# stickie.net
KiCad netlist of a schematic drawn in EAGLE
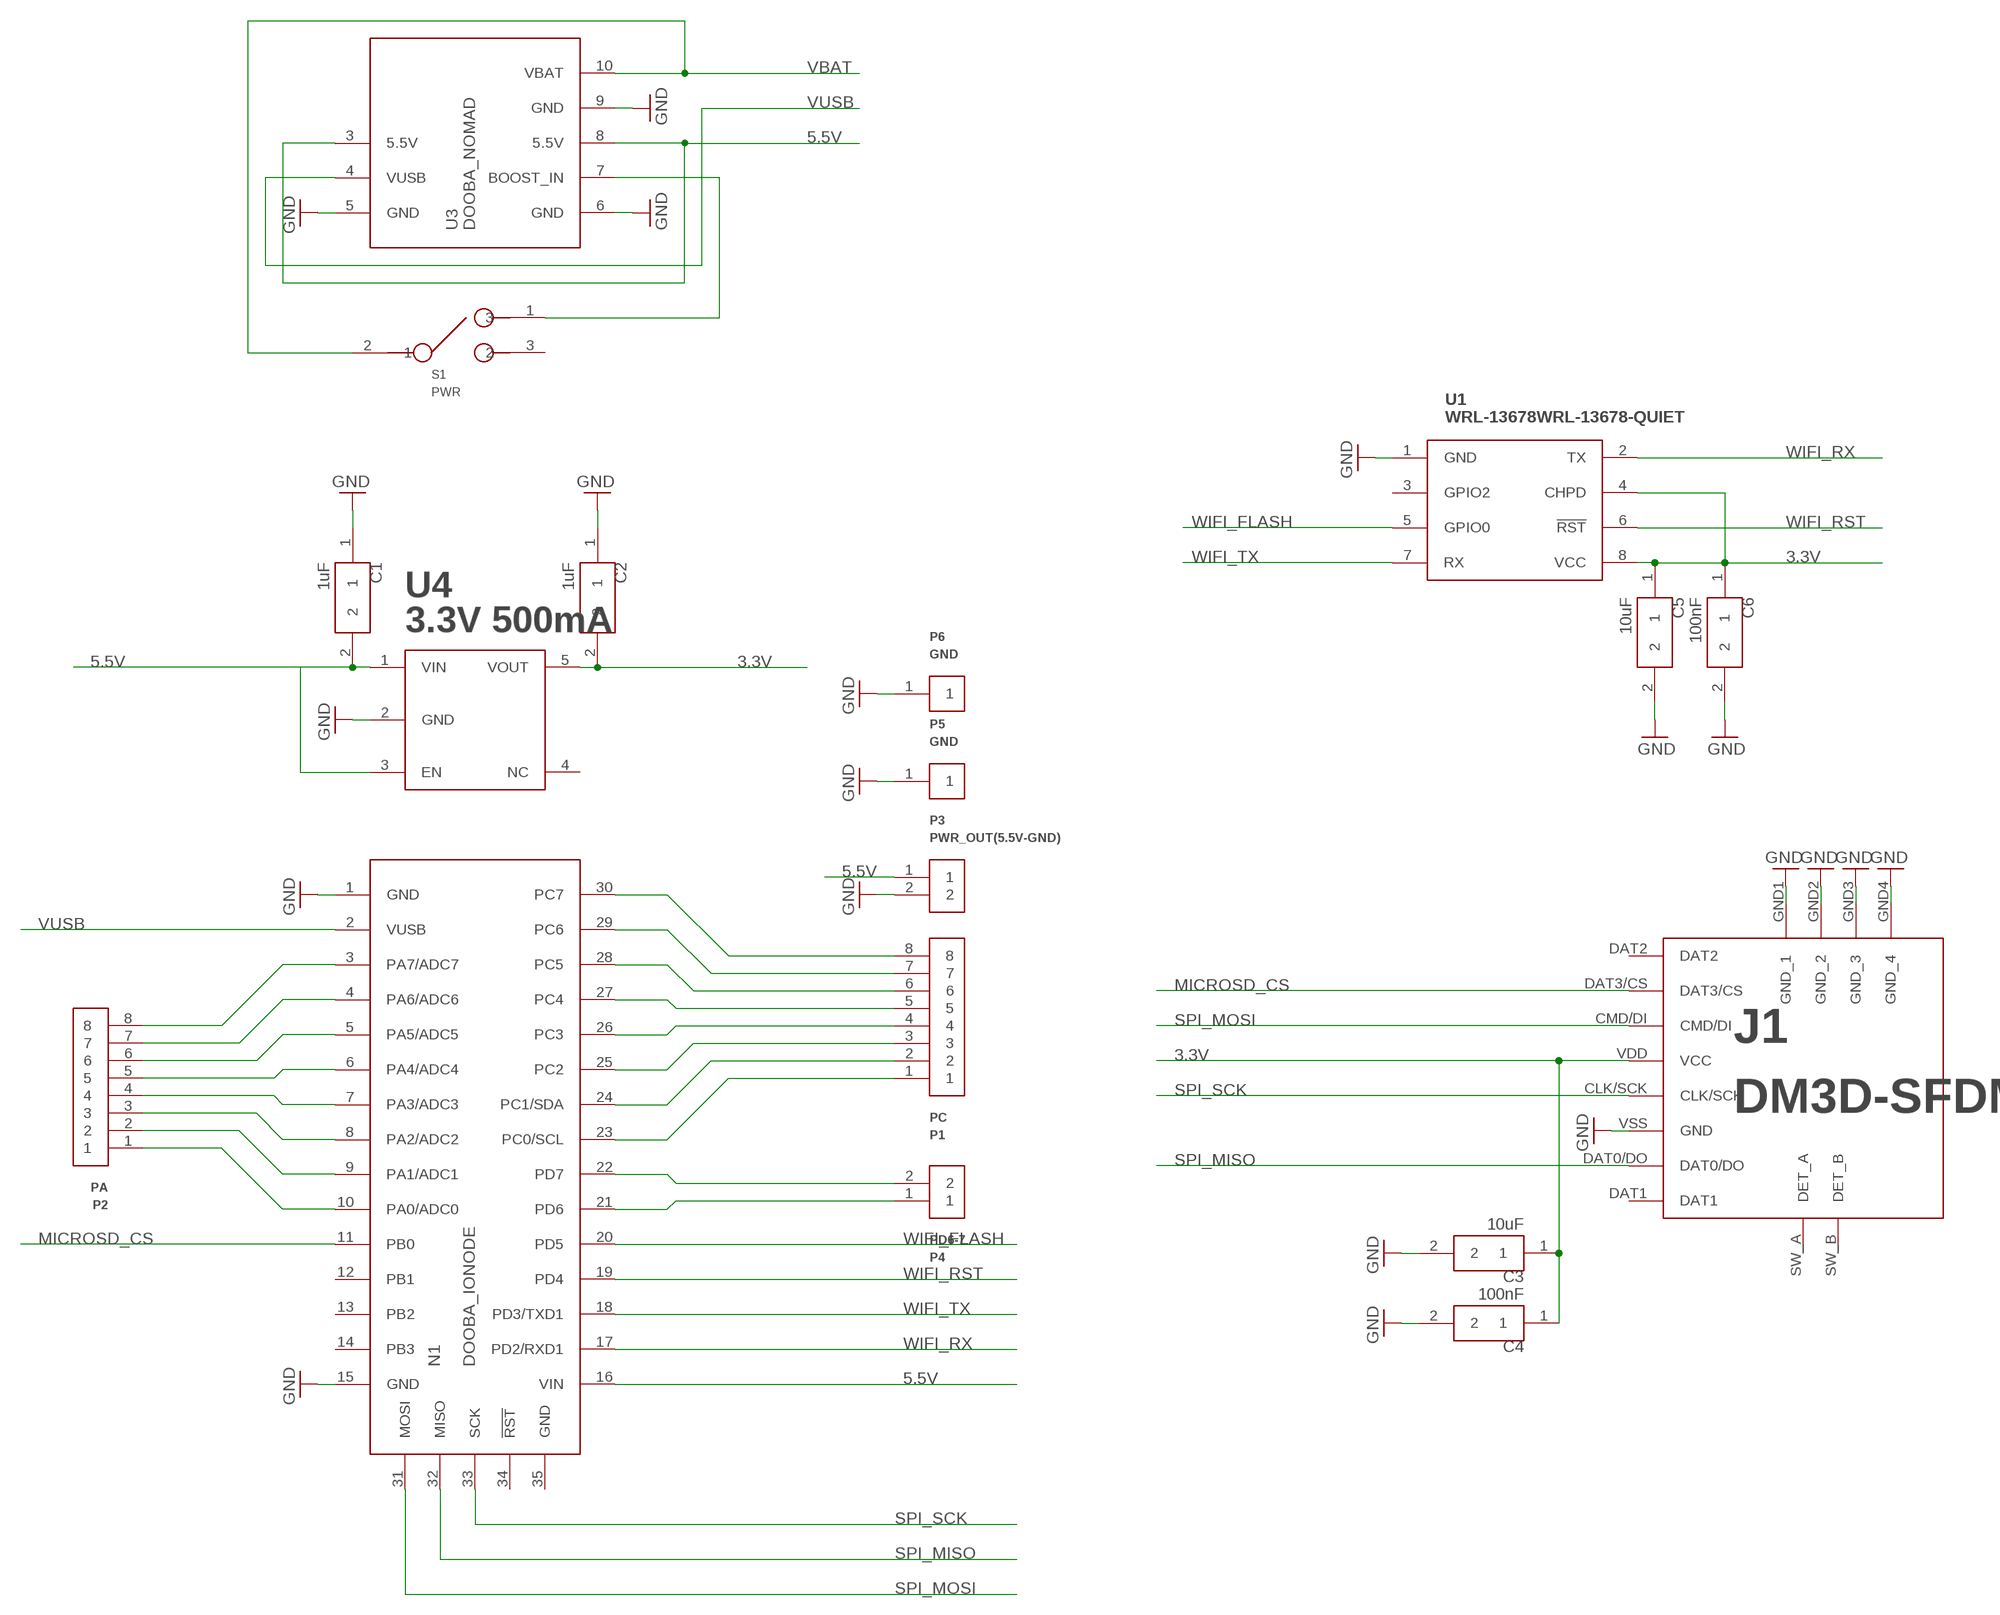
[diagram p0: schematic, sheet 1]

(export (version "E")
  (design (tool "Eeschema 10.0.6"))
  (components
    (comp (ref "C1")
      (value "1uF")
      (footprint "eagle-import:0805")
      (libsource (lib "eagle-import") (part "CAP0805"))
    )
    (comp (ref "C2")
      (value "1uF")
      (footprint "eagle-import:0805")
      (libsource (lib "eagle-import") (part "CAP0805"))
    )
    (comp (ref "C3")
      (value "10uF")
      (footprint "eagle-import:0805")
      (libsource (lib "eagle-import") (part "CAP0805"))
    )
    (comp (ref "C4")
      (value "100nF")
      (footprint "eagle-import:0805")
      (libsource (lib "eagle-import") (part "CAP0805"))
    )
    (comp (ref "C5")
      (value "10uF")
      (footprint "eagle-import:0805")
      (libsource (lib "eagle-import") (part "CAP0805"))
    )
    (comp (ref "C6")
      (value "100nF")
      (footprint "eagle-import:0805")
      (libsource (lib "eagle-import") (part "CAP0805"))
    )
    (comp (ref "J1")
      (value "DM3D-SFDM")
      (footprint "eagle-import:DM3D-SF")
      (libsource (lib "eagle-import") (part "DM3D-SFDM"))
    )
    (comp (ref "N1")
      (value "DOOBA_IONODE")
      (footprint "eagle-import:DOOBA_IONODE")
      (libsource (lib "eagle-import") (part "DOOBA_IONODE"))
    )
    (comp (ref "P1")
      (value "PC")
      (footprint "eagle-import:PIN_8")
      (libsource (lib "eagle-import") (part "PIN_8"))
    )
    (comp (ref "P2")
      (value "PA")
      (footprint "eagle-import:PIN_8")
      (libsource (lib "eagle-import") (part "PIN_8"))
    )
    (comp (ref "P3")
      (value "PWR_OUT(5.5V-GND)")
      (footprint "eagle-import:PIN_2")
      (libsource (lib "eagle-import") (part "PIN_2"))
    )
    (comp (ref "P4")
      (value "PD6-7")
      (footprint "eagle-import:PIN_2")
      (libsource (lib "eagle-import") (part "PIN_2"))
    )
    (comp (ref "P5")
      (value "GND")
      (footprint "eagle-import:PIN_1")
      (libsource (lib "eagle-import") (part "PIN_1"))
    )
    (comp (ref "P6")
      (value "GND")
      (footprint "eagle-import:PIN_1")
      (libsource (lib "eagle-import") (part "PIN_1"))
    )
    (comp (ref "S1")
      (value "PWR")
      (footprint "eagle-import:JS102011")
      (libsource (lib "eagle-import") (part "SWITCH_SPDT"))
    )
    (comp (ref "U1")
      (value "WRL-13678WRL-13678-QUIET")
      (footprint "eagle-import:WRL-13678-QUIET")
      (libsource (lib "eagle-import") (part "WRL-13678WRL-13678-QUIET"))
    )
    (comp (ref "U3")
      (value "DOOBA_NOMAD")
      (footprint "eagle-import:DOOBA_NOMAD")
      (libsource (lib "eagle-import") (part "DOOBA_NOMAD"))
    )
    (comp (ref "U4")
      (value "3.3V 500mA")
      (footprint "eagle-import:SOT23-5")
      (libsource (lib "eagle-import") (part "LP3985SOT23-5"))
    )
  )
  (nets
    (net (code "1") (name "/3.3V") (class "Default")
      (node (ref "C2") (pin "2") (pinfunction "2_2") (pintype "bidirectional"))
      (node (ref "C3") (pin "1") (pinfunction "1_1") (pintype "bidirectional"))
      (node (ref "C4") (pin "1") (pinfunction "1_1") (pintype "bidirectional"))
      (node (ref "C5") (pin "1") (pinfunction "1_1") (pintype "bidirectional"))
      (node (ref "C6") (pin "1") (pinfunction "1_1") (pintype "bidirectional"))
      (node (ref "J1") (pin "VDD") (pinfunction "VCC_VDD") (pintype "bidirectional"))
      (node (ref "U1") (pin "4") (pinfunction "CHPD_4") (pintype "bidirectional"))
      (node (ref "U1") (pin "8") (pinfunction "VCC_8") (pintype "bidirectional"))
      (node (ref "U4") (pin "5") (pinfunction "VOUT_5") (pintype "bidirectional"))
    )
    (net (code "2") (name "/5.5V") (class "Default")
      (node (ref "C1") (pin "2") (pinfunction "2_2") (pintype "bidirectional"))
      (node (ref "N1") (pin "16") (pinfunction "VIN_16") (pintype "bidirectional"))
      (node (ref "P3") (pin "1") (pinfunction "1_1") (pintype "bidirectional"))
      (node (ref "U3") (pin "3") (pinfunction "5.5V_3") (pintype "bidirectional"))
      (node (ref "U3") (pin "8") (pinfunction "5.5V_8") (pintype "bidirectional"))
      (node (ref "U4") (pin "1") (pinfunction "VIN_1") (pintype "bidirectional"))
      (node (ref "U4") (pin "3") (pinfunction "EN_3") (pintype "bidirectional"))
    )
    (net (code "3") (name "/MICROSD_CS") (class "Default")
      (node (ref "J1") (pin "DAT3/CS") (pinfunction "DAT3/CS_DAT3/CS") (pintype "bidirectional"))
      (node (ref "N1") (pin "11") (pinfunction "PB0_11") (pintype "bidirectional"))
    )
    (net (code "4") (name "/SPI_MISO") (class "Default")
      (node (ref "J1") (pin "DAT0/DO") (pinfunction "DAT0/DO_DAT0/DO") (pintype "bidirectional"))
      (node (ref "N1") (pin "32") (pinfunction "MISO_32") (pintype "bidirectional"))
    )
    (net (code "5") (name "/SPI_MOSI") (class "Default")
      (node (ref "J1") (pin "CMD/DI") (pinfunction "CMD/DI_CMD/DI") (pintype "bidirectional"))
      (node (ref "N1") (pin "31") (pinfunction "MOSI_31") (pintype "bidirectional"))
    )
    (net (code "6") (name "/SPI_SCK") (class "Default")
      (node (ref "J1") (pin "CLK/SCK") (pinfunction "CLK/SCK_CLK/SCK") (pintype "bidirectional"))
      (node (ref "N1") (pin "33") (pinfunction "SCK_33") (pintype "bidirectional"))
    )
    (net (code "7") (name "/VBAT") (class "Default")
      (node (ref "S1") (pin "2") (pinfunction "1_2") (pintype "bidirectional"))
      (node (ref "U3") (pin "10") (pinfunction "VBAT_10") (pintype "bidirectional"))
    )
    (net (code "8") (name "/VUSB") (class "Default")
      (node (ref "N1") (pin "2") (pinfunction "VUSB_2") (pintype "bidirectional"))
      (node (ref "U3") (pin "4") (pinfunction "VUSB_4") (pintype "bidirectional"))
    )
    (net (code "9") (name "/WIFI_FLASH") (class "Default")
      (node (ref "N1") (pin "20") (pinfunction "PD5_20") (pintype "bidirectional"))
      (node (ref "U1") (pin "5") (pinfunction "GPIO0_5") (pintype "bidirectional"))
    )
    (net (code "10") (name "/WIFI_RST") (class "Default")
      (node (ref "N1") (pin "19") (pinfunction "PD4_19") (pintype "bidirectional"))
      (node (ref "U1") (pin "6") (pinfunction "~{RST}_6") (pintype "bidirectional"))
    )
    (net (code "11") (name "/WIFI_RX") (class "Default")
      (node (ref "N1") (pin "17") (pinfunction "PD2/RXD1_17") (pintype "bidirectional"))
      (node (ref "U1") (pin "2") (pinfunction "TX_2") (pintype "bidirectional"))
    )
    (net (code "12") (name "/WIFI_TX") (class "Default")
      (node (ref "N1") (pin "18") (pinfunction "PD3/TXD1_18") (pintype "bidirectional"))
      (node (ref "U1") (pin "7") (pinfunction "RX_7") (pintype "bidirectional"))
    )
    (net (code "13") (name "GND") (class "Default")
      (node (ref "C1") (pin "1") (pinfunction "1_1") (pintype "bidirectional"))
      (node (ref "C2") (pin "1") (pinfunction "1_1") (pintype "bidirectional"))
      (node (ref "C3") (pin "2") (pinfunction "2_2") (pintype "bidirectional"))
      (node (ref "C4") (pin "2") (pinfunction "2_2") (pintype "bidirectional"))
      (node (ref "C5") (pin "2") (pinfunction "2_2") (pintype "bidirectional"))
      (node (ref "C6") (pin "2") (pinfunction "2_2") (pintype "bidirectional"))
      (node (ref "J1") (pin "GND1") (pinfunction "GND_1_GND1") (pintype "bidirectional"))
      (node (ref "J1") (pin "GND2") (pinfunction "GND_2_GND2") (pintype "bidirectional"))
      (node (ref "J1") (pin "GND3") (pinfunction "GND_3_GND3") (pintype "bidirectional"))
      (node (ref "J1") (pin "GND4") (pinfunction "GND_4_GND4") (pintype "bidirectional"))
      (node (ref "J1") (pin "VSS") (pinfunction "GND_VSS") (pintype "bidirectional"))
      (node (ref "N1") (pin "1") (pinfunction "GND_1") (pintype "bidirectional"))
      (node (ref "N1") (pin "15") (pinfunction "GND_15") (pintype "bidirectional"))
      (node (ref "P3") (pin "2") (pinfunction "2_2") (pintype "bidirectional"))
      (node (ref "P5") (pin "1") (pinfunction "1_1") (pintype "bidirectional"))
      (node (ref "P6") (pin "1") (pinfunction "1_1") (pintype "bidirectional"))
      (node (ref "U1") (pin "1") (pinfunction "GND_1") (pintype "bidirectional"))
      (node (ref "U3") (pin "5") (pinfunction "GND_5") (pintype "bidirectional"))
      (node (ref "U3") (pin "6") (pinfunction "GND_6") (pintype "bidirectional"))
      (node (ref "U3") (pin "9") (pinfunction "GND_9") (pintype "bidirectional"))
      (node (ref "U4") (pin "2") (pinfunction "GND_2") (pintype "bidirectional"))
    )
    (net (code "14") (name "Net-(N1-PA0{slash}ADC0)") (class "Default")
      (node (ref "N1") (pin "10") (pinfunction "PA0/ADC0_10") (pintype "bidirectional"))
      (node (ref "P2") (pin "1") (pinfunction "1_1") (pintype "bidirectional"))
    )
    (net (code "15") (name "Net-(N1-PA1{slash}ADC1)") (class "Default")
      (node (ref "N1") (pin "9") (pinfunction "PA1/ADC1_9") (pintype "bidirectional"))
      (node (ref "P2") (pin "2") (pinfunction "2_2") (pintype "bidirectional"))
    )
    (net (code "16") (name "Net-(N1-PA2{slash}ADC2)") (class "Default")
      (node (ref "N1") (pin "8") (pinfunction "PA2/ADC2_8") (pintype "bidirectional"))
      (node (ref "P2") (pin "3") (pinfunction "3_3") (pintype "bidirectional"))
    )
    (net (code "17") (name "Net-(N1-PA3{slash}ADC3)") (class "Default")
      (node (ref "N1") (pin "7") (pinfunction "PA3/ADC3_7") (pintype "bidirectional"))
      (node (ref "P2") (pin "4") (pinfunction "4_4") (pintype "bidirectional"))
    )
    (net (code "18") (name "Net-(N1-PA4{slash}ADC4)") (class "Default")
      (node (ref "N1") (pin "6") (pinfunction "PA4/ADC4_6") (pintype "bidirectional"))
      (node (ref "P2") (pin "5") (pinfunction "5_5") (pintype "bidirectional"))
    )
    (net (code "19") (name "Net-(N1-PA5{slash}ADC5)") (class "Default")
      (node (ref "N1") (pin "5") (pinfunction "PA5/ADC5_5") (pintype "bidirectional"))
      (node (ref "P2") (pin "6") (pinfunction "6_6") (pintype "bidirectional"))
    )
    (net (code "20") (name "Net-(N1-PA6{slash}ADC6)") (class "Default")
      (node (ref "N1") (pin "4") (pinfunction "PA6/ADC6_4") (pintype "bidirectional"))
      (node (ref "P2") (pin "7") (pinfunction "7_7") (pintype "bidirectional"))
    )
    (net (code "21") (name "Net-(N1-PA7{slash}ADC7)") (class "Default")
      (node (ref "N1") (pin "3") (pinfunction "PA7/ADC7_3") (pintype "bidirectional"))
      (node (ref "P2") (pin "8") (pinfunction "8_8") (pintype "bidirectional"))
    )
    (net (code "22") (name "Net-(N1-PC0{slash}SCL)") (class "Default")
      (node (ref "N1") (pin "23") (pinfunction "PC0/SCL_23") (pintype "bidirectional"))
      (node (ref "P1") (pin "1") (pinfunction "1_1") (pintype "bidirectional"))
    )
    (net (code "23") (name "Net-(N1-PC1{slash}SDA)") (class "Default")
      (node (ref "N1") (pin "24") (pinfunction "PC1/SDA_24") (pintype "bidirectional"))
      (node (ref "P1") (pin "2") (pinfunction "2_2") (pintype "bidirectional"))
    )
    (net (code "24") (name "Net-(N1-PC2)") (class "Default")
      (node (ref "N1") (pin "25") (pinfunction "PC2_25") (pintype "bidirectional"))
      (node (ref "P1") (pin "3") (pinfunction "3_3") (pintype "bidirectional"))
    )
    (net (code "25") (name "Net-(N1-PC3)") (class "Default")
      (node (ref "N1") (pin "26") (pinfunction "PC3_26") (pintype "bidirectional"))
      (node (ref "P1") (pin "4") (pinfunction "4_4") (pintype "bidirectional"))
    )
    (net (code "26") (name "Net-(N1-PC4)") (class "Default")
      (node (ref "N1") (pin "27") (pinfunction "PC4_27") (pintype "bidirectional"))
      (node (ref "P1") (pin "5") (pinfunction "5_5") (pintype "bidirectional"))
    )
    (net (code "27") (name "Net-(N1-PC5)") (class "Default")
      (node (ref "N1") (pin "28") (pinfunction "PC5_28") (pintype "bidirectional"))
      (node (ref "P1") (pin "6") (pinfunction "6_6") (pintype "bidirectional"))
    )
    (net (code "28") (name "Net-(N1-PC6)") (class "Default")
      (node (ref "N1") (pin "29") (pinfunction "PC6_29") (pintype "bidirectional"))
      (node (ref "P1") (pin "7") (pinfunction "7_7") (pintype "bidirectional"))
    )
    (net (code "29") (name "Net-(N1-PC7)") (class "Default")
      (node (ref "N1") (pin "30") (pinfunction "PC7_30") (pintype "bidirectional"))
      (node (ref "P1") (pin "8") (pinfunction "8_8") (pintype "bidirectional"))
    )
    (net (code "30") (name "Net-(N1-PD6)") (class "Default")
      (node (ref "N1") (pin "21") (pinfunction "PD6_21") (pintype "bidirectional"))
      (node (ref "P4") (pin "1") (pinfunction "1_1") (pintype "bidirectional"))
    )
    (net (code "31") (name "Net-(N1-PD7)") (class "Default")
      (node (ref "N1") (pin "22") (pinfunction "PD7_22") (pintype "bidirectional"))
      (node (ref "P4") (pin "2") (pinfunction "2_2") (pintype "bidirectional"))
    )
    (net (code "32") (name "Net-(S1-3)") (class "Default")
      (node (ref "S1") (pin "1") (pinfunction "3_1") (pintype "bidirectional"))
      (node (ref "U3") (pin "7") (pinfunction "BOOST_IN_7") (pintype "bidirectional"))
    )
    (net (code "33") (name "unconnected-(J1-DET_A-PadSW_A)") (class "Default")
      (node (ref "J1") (pin "SW_A") (pinfunction "DET_A_SW_A") (pintype "bidirectional"))
    )
    (net (code "34") (name "unconnected-(J1-DET_B-PadSW_B)") (class "Default")
      (node (ref "J1") (pin "SW_B") (pinfunction "DET_B_SW_B") (pintype "bidirectional"))
    )
    (net (code "35") (name "unconnected-(J1-PadDAT1)") (class "Default")
      (node (ref "J1") (pin "DAT1") (pinfunction "DAT1_DAT1") (pintype "bidirectional"))
    )
    (net (code "36") (name "unconnected-(J1-PadDAT2)") (class "Default")
      (node (ref "J1") (pin "DAT2") (pinfunction "DAT2_DAT2") (pintype "bidirectional"))
    )
    (net (code "37") (name "unconnected-(N1-GND-Pad35)") (class "Default")
      (node (ref "N1") (pin "35") (pinfunction "GND_35") (pintype "bidirectional"))
    )
    (net (code "38") (name "unconnected-(N1-PB1-Pad12)") (class "Default")
      (node (ref "N1") (pin "12") (pinfunction "PB1_12") (pintype "bidirectional"))
    )
    (net (code "39") (name "unconnected-(N1-PB2-Pad13)") (class "Default")
      (node (ref "N1") (pin "13") (pinfunction "PB2_13") (pintype "bidirectional"))
    )
    (net (code "40") (name "unconnected-(N1-PB3-Pad14)") (class "Default")
      (node (ref "N1") (pin "14") (pinfunction "PB3_14") (pintype "bidirectional"))
    )
    (net (code "41") (name "unconnected-(N1-~{RST}-Pad34)") (class "Default")
      (node (ref "N1") (pin "34") (pinfunction "~{RST}_34") (pintype "bidirectional"))
    )
    (net (code "42") (name "unconnected-(S1-2-Pad3)") (class "Default")
      (node (ref "S1") (pin "3") (pinfunction "2_3") (pintype "bidirectional"))
    )
    (net (code "43") (name "unconnected-(U1-GPIO2-Pad3)") (class "Default")
      (node (ref "U1") (pin "3") (pinfunction "GPIO2_3") (pintype "bidirectional"))
    )
    (net (code "44") (name "unconnected-(U4-NC-Pad4)") (class "Default")
      (node (ref "U4") (pin "4") (pinfunction "NC_4") (pintype "bidirectional"))
    )
  )
)
